# INA190.net
KiCad netlist of a schematic drawn in Altium Designer
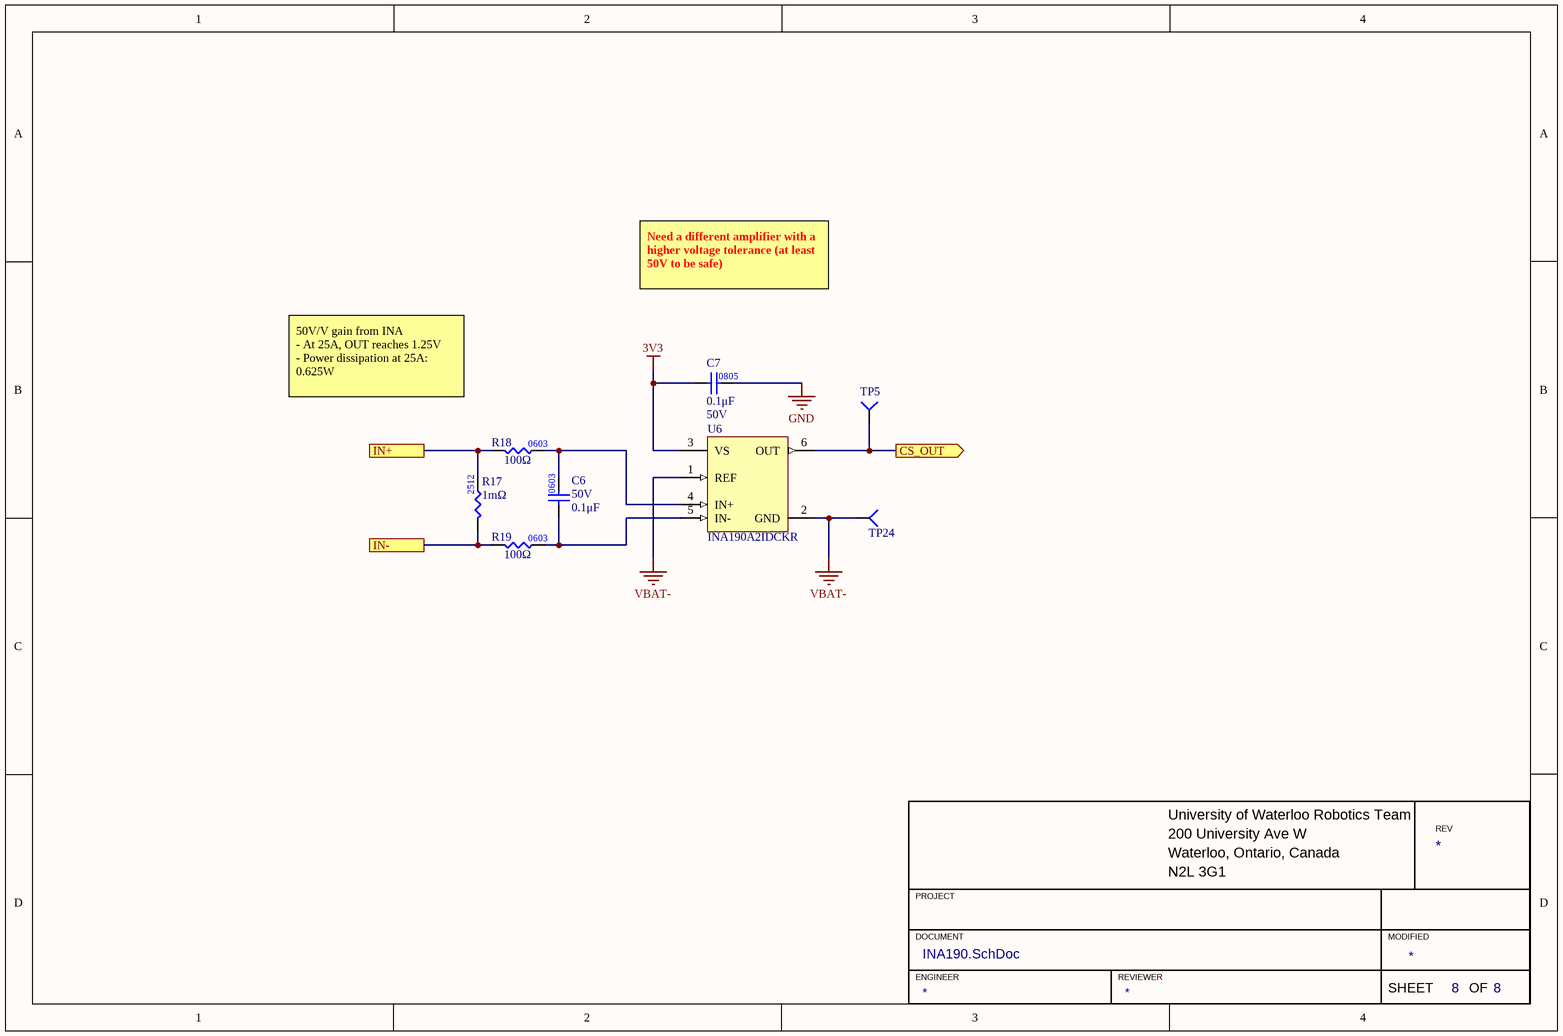
[diagram p0: INA190.SchDoc]

(export (version "E")
  (design (tool "Eeschema 10.0.6"))
  (components
    (comp (ref "C6")
      (value "0.1μF")
      (footprint "CAP0603")
      (description "CAP CER 0.1UF 50V X7R 0603")
      (fields (field (name "VOLTAGE RATING") "50V") (field (name "Comment") "CAP_0.1uF_50V_0603"))
      (libsource (lib "Personal_Schematic_Library_2022") (part "CAP_0.1uF_50V_0603"))
    )
    (comp (ref "C7")
      (value "0.1μF")
      (footprint "CAP0805")
      (description "CAP CER 0.1UF 50V X7R 0805")
      (fields
        (field (name "VOLTAGE RATING") "50V")
        (field (name "LCSC PART #") "C49678")
        (field (name "Comment") "CAP_0.1uF_50V_0805")
      )
      (libsource (lib "UWRT_Schematic_Library_2020") (part "CAP_0.1uF_50V_0805"))
    )
    (comp (ref "R17")
      (value "1mΩ")
      (footprint "RESC6532X75N")
      (description "RES 1 mOHM 1% 3W 2512")
      (fields (field (name "Comment") "RES_1mΩ_2512_1%"))
      (libsource (lib "UWRT_Schematic_Library_2020") (part "RES_1mΩ_2512_1%"))
    )
    (comp (ref "R18")
      (value "100Ω")
      (footprint "RES0603")
      (description "RES 100 OHM 1% 1/10W 0603")
      (fields (field (name "Comment") "RES_100Ω_0603_1%"))
      (libsource (lib "Personal_Schematic_Library_2022") (part "RES_100Ω_0603_1%"))
    )
    (comp (ref "R19")
      (value "100Ω")
      (footprint "RES0603")
      (description "RES 100 OHM 1% 1/10W 0603")
      (fields (field (name "Comment") "RES_100Ω_0603_1%"))
      (libsource (lib "Personal_Schematic_Library_2022") (part "RES_100Ω_0603_1%"))
    )
    (comp (ref "TP5")
      (value "TESTPOINT_1MM_CIRCLE")
      (footprint "TESTPOINT_CIRCLE_1MM")
      (description "TESTPOINT 1MM CIRCLE")
      (libsource (lib "UWRT_Schematic_Library_2020") (part "TESTPOINT_1MM_CIRCLE"))
    )
    (comp (ref "TP24")
      (value "TESTPOINT_SMD_LOOP")
      (footprint "S1751-46R")
      (description "TESTPOINT SMD LOOP")
      (libsource (lib "UWRT_Schematic_Library_2020") (part "TESTPOINT_SMD_LOOP"))
    )
    (comp (ref "U6")
      (value "INA190A2IDCKR")
      (footprint "TI_SC-70-6")
      (description "IC CURR SENSE 1 CIRCUIT SC70-6")
      (fields (field (name "MANUFACTURER PART NUMBER 1") "INA190A2IDCKR"))
      (libsource (lib "Personal_Schematic_Library_2022") (part "INA190A2IDCKR"))
    )
  )
  (nets
    (net (code "1") (name "/CS_OUT") (class "Default")
      (node (ref "TP5") (pin "1") (pinfunction "=value_1") (pintype "passive"))
      (node (ref "U6") (pin "6") (pinfunction "OUT_6") (pintype "output"))
    )
    (net (code "2") (name "/IN+") (class "Default")
      (node (ref "R17") (pin "2") (pinfunction "2_2") (pintype "passive"))
      (node (ref "R18") (pin "1") (pinfunction "1_1") (pintype "passive"))
    )
    (net (code "3") (name "/IN-") (class "Default")
      (node (ref "R17") (pin "1") (pinfunction "1_1") (pintype "passive"))
      (node (ref "R19") (pin "1") (pinfunction "1_1") (pintype "passive"))
    )
    (net (code "4") (name "3V3") (class "Default")
      (node (ref "C7") (pin "1") (pinfunction "1_1") (pintype "passive"))
      (node (ref "U6") (pin "3") (pinfunction "VS_3") (pintype "power_in"))
    )
    (net (code "5") (name "GND") (class "Default")
      (node (ref "C7") (pin "2") (pinfunction "2_2") (pintype "passive"))
    )
    (net (code "6") (name "Net-(U6-IN+)") (class "Default")
      (node (ref "C6") (pin "2") (pinfunction "2_2") (pintype "passive"))
      (node (ref "R18") (pin "2") (pinfunction "2_2") (pintype "passive"))
      (node (ref "U6") (pin "4") (pinfunction "IN+_4") (pintype "input"))
    )
    (net (code "7") (name "Net-(U6-IN-)") (class "Default")
      (node (ref "C6") (pin "1") (pinfunction "1_1") (pintype "passive"))
      (node (ref "R19") (pin "2") (pinfunction "2_2") (pintype "passive"))
      (node (ref "U6") (pin "5") (pinfunction "IN-_5") (pintype "input"))
    )
    (net (code "8") (name "VBAT-") (class "Default")
      (node (ref "TP24") (pin "1") (pinfunction "=value_1") (pintype "passive"))
      (node (ref "U6") (pin "1") (pinfunction "REF_1") (pintype "input"))
      (node (ref "U6") (pin "2") (pinfunction "GND_2") (pintype "passive"))
    )
  )
)
